# STM32F407VG.net
KiCad netlist of a schematic drawn in EasyEDA Pro
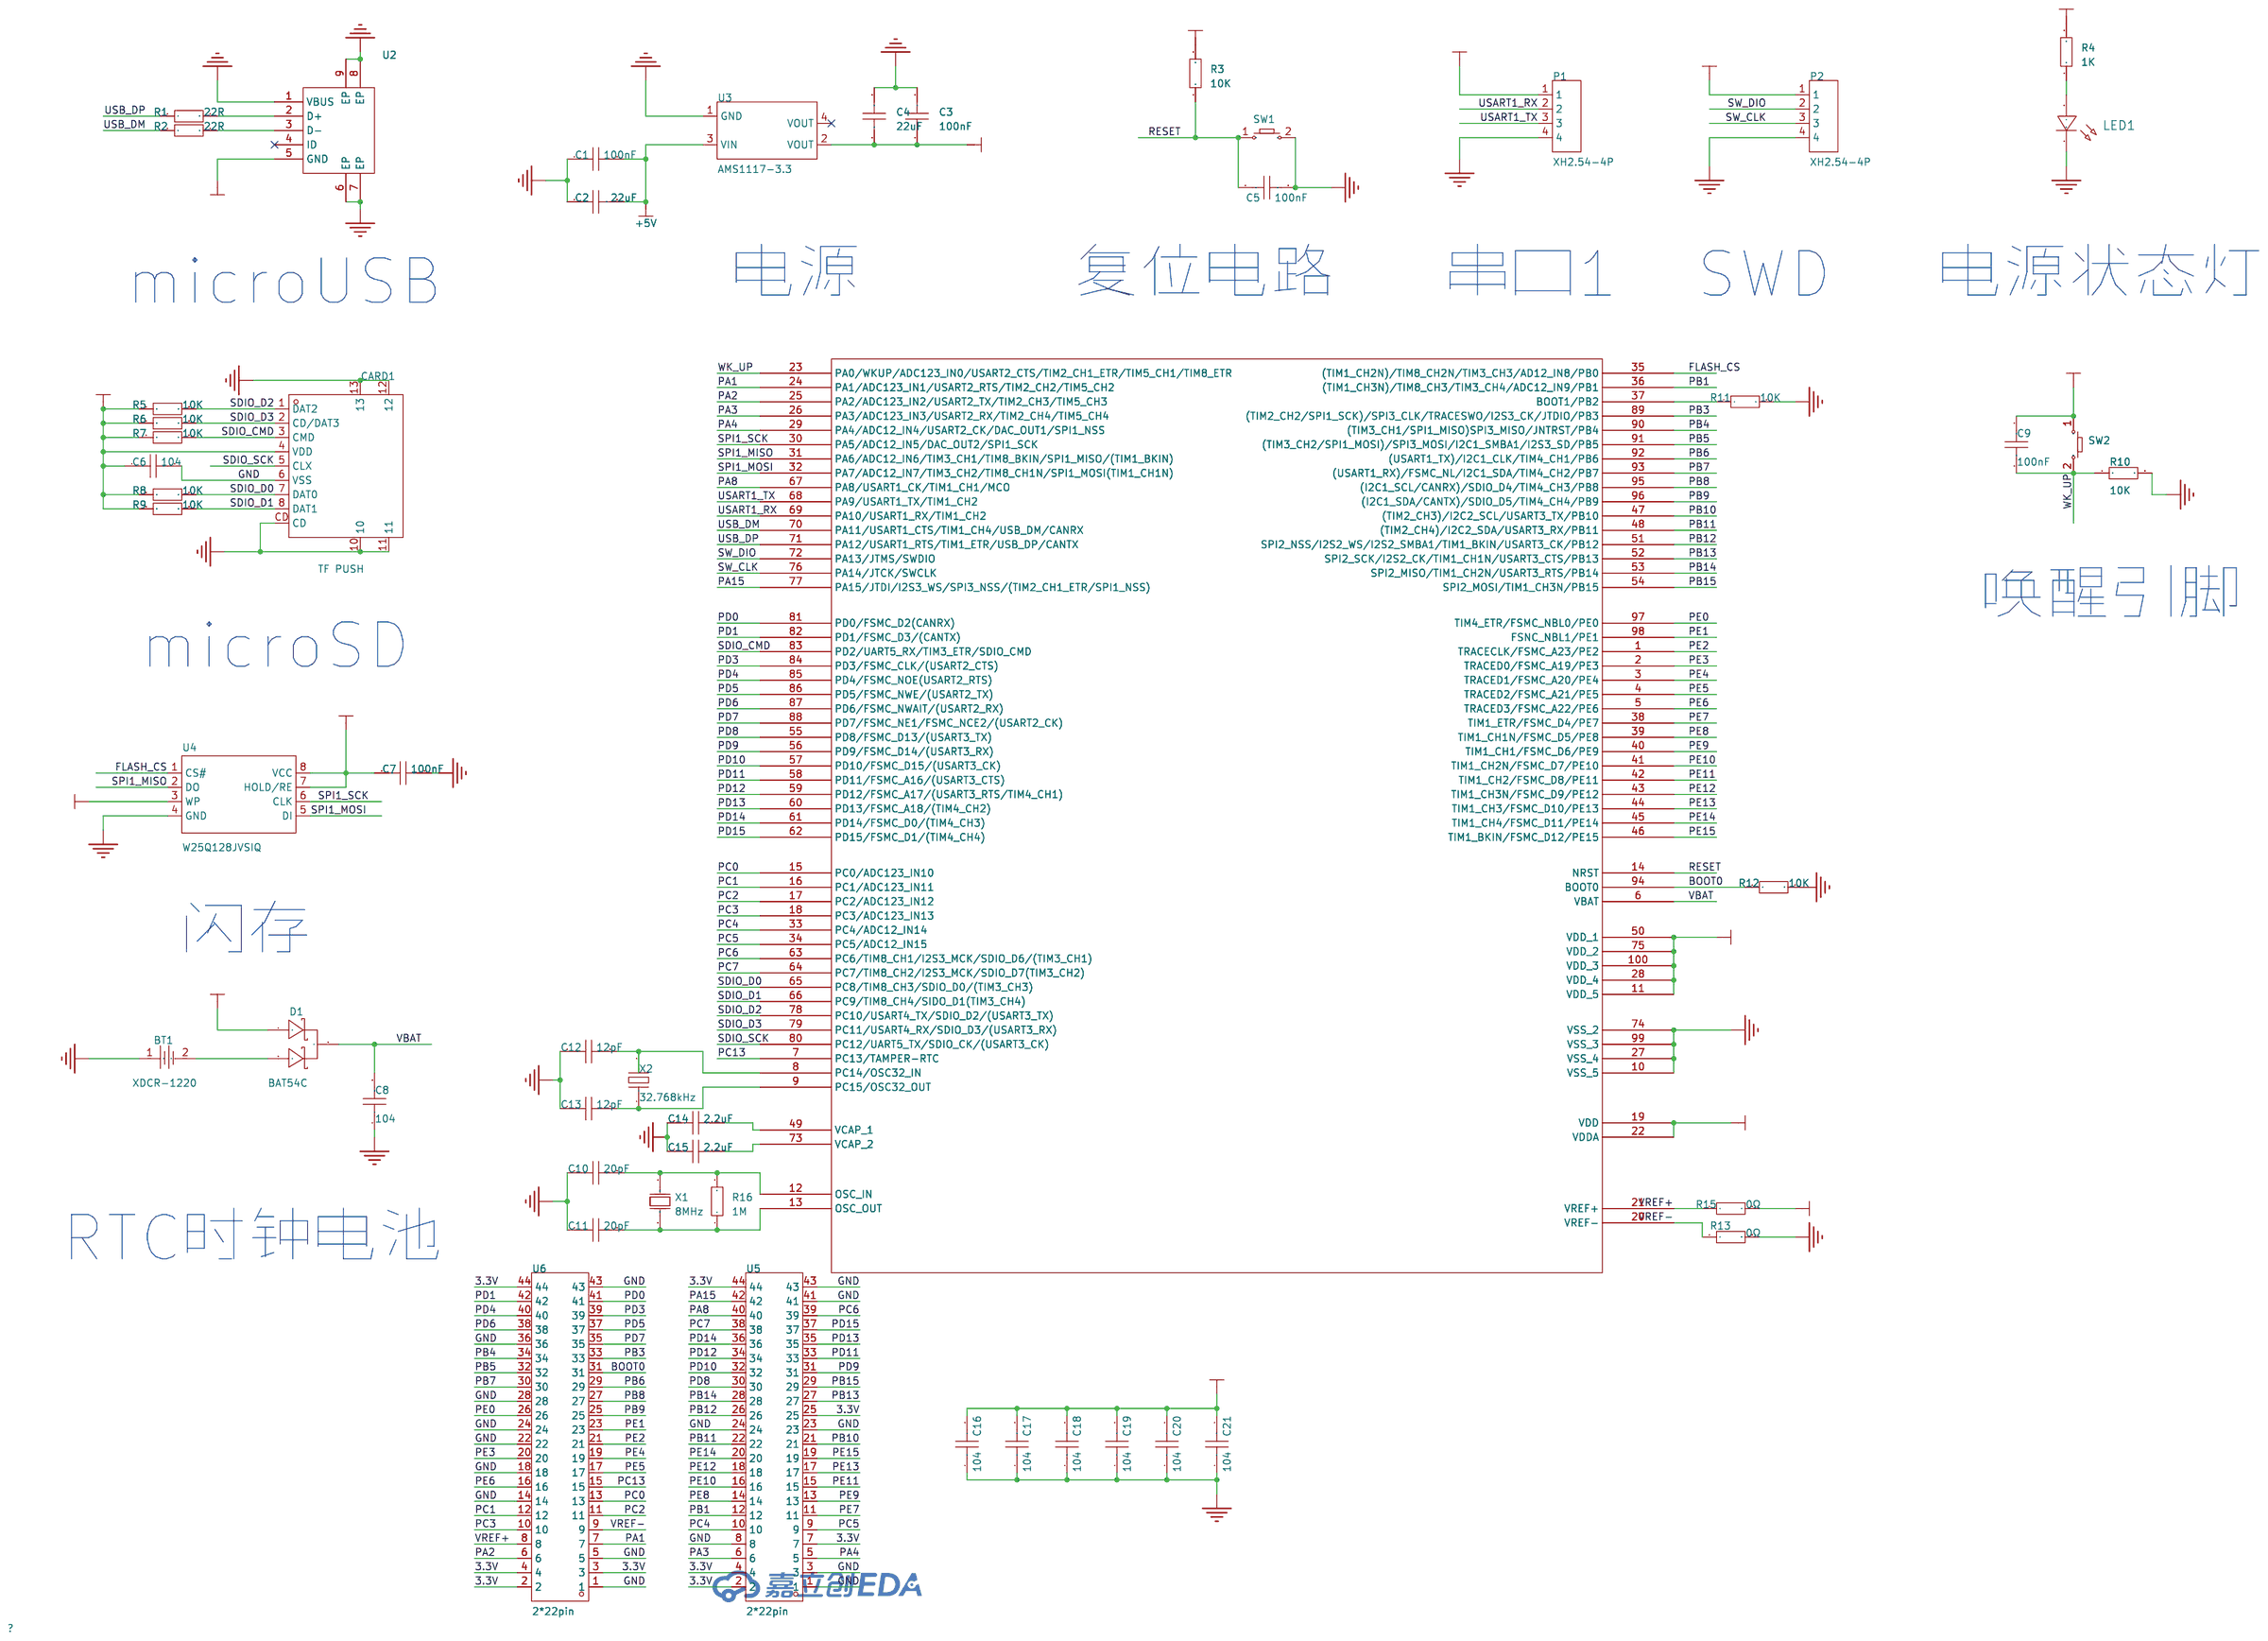
[diagram p0: schematic sheet]

(export (version "E")
  (design (tool "Eeschema 10.0.6"))
  (components
    (comp (ref "BT1")
      (value "XDCR-1220")
      (footprint "easyedapro:BAT-SMD_CR1220-2ZX")
      (description "连接器类型:电池底座;适用电池规格:CR1220;触头材质:-;触头镀层:金;工作温度:-40°C~+85°C;")
      (fields (field (name "Manufacturer") "LX(连欣科技)"))
      (libsource (lib "easyedapro") (part "XDCR-1220-006"))
    )
    (comp (ref "C1")
      (value "100nF")
      (footprint "easyedapro:C0603")
      (libsource (lib "easyedapro") (part "CapAcitance"))
    )
    (comp (ref "C2")
      (value "22uF")
      (footprint "easyedapro:C0603")
      (libsource (lib "easyedapro") (part "CapAcitance"))
    )
    (comp (ref "C3")
      (value "100nF")
      (footprint "easyedapro:C0603")
      (libsource (lib "easyedapro") (part "CapAcitance"))
    )
    (comp (ref "C4")
      (value "22uF")
      (footprint "easyedapro:C0603")
      (libsource (lib "easyedapro") (part "CapAcitance"))
    )
    (comp (ref "C5")
      (value "100nF")
      (footprint "easyedapro:C0603")
      (libsource (lib "easyedapro") (part "CapAcitance"))
    )
    (comp (ref "C6")
      (value "104")
      (footprint "easyedapro:C0603")
      (libsource (lib "easyedapro") (part "CapAcitance"))
    )
    (comp (ref "C7")
      (value "100nF")
      (footprint "easyedapro:C0603")
      (libsource (lib "easyedapro") (part "CapAcitance"))
    )
    (comp (ref "C8")
      (value "104")
      (footprint "easyedapro:C0603")
      (libsource (lib "easyedapro") (part "CapAcitance"))
    )
    (comp (ref "C9")
      (value "100nF")
      (footprint "easyedapro:C0603")
      (libsource (lib "easyedapro") (part "CapAcitance"))
    )
    (comp (ref "C10")
      (value "20pF")
      (footprint "easyedapro:C0603")
      (libsource (lib "easyedapro") (part "CapAcitance"))
    )
    (comp (ref "C11")
      (value "20pF")
      (footprint "easyedapro:C0603")
      (libsource (lib "easyedapro") (part "CapAcitance"))
    )
    (comp (ref "C12")
      (value "12pF")
      (footprint "easyedapro:C0603")
      (libsource (lib "easyedapro") (part "CapAcitance"))
    )
    (comp (ref "C13")
      (value "12pF")
      (footprint "easyedapro:C0603")
      (libsource (lib "easyedapro") (part "CapAcitance"))
    )
    (comp (ref "C14")
      (value "2.2uF")
      (footprint "easyedapro:C0603")
      (libsource (lib "easyedapro") (part "CapAcitance"))
    )
    (comp (ref "C15")
      (value "2.2uF")
      (footprint "easyedapro:C0603")
      (libsource (lib "easyedapro") (part "CapAcitance"))
    )
    (comp (ref "C16")
      (value "104")
      (footprint "easyedapro:C0603")
      (libsource (lib "easyedapro") (part "CapAcitance"))
    )
    (comp (ref "C17")
      (value "104")
      (footprint "easyedapro:C0603")
      (libsource (lib "easyedapro") (part "CapAcitance"))
    )
    (comp (ref "C18")
      (value "104")
      (footprint "easyedapro:C0603")
      (libsource (lib "easyedapro") (part "CapAcitance"))
    )
    (comp (ref "C19")
      (value "104")
      (footprint "easyedapro:C0603")
      (libsource (lib "easyedapro") (part "CapAcitance"))
    )
    (comp (ref "C20")
      (value "104")
      (footprint "easyedapro:C0603")
      (libsource (lib "easyedapro") (part "CapAcitance"))
    )
    (comp (ref "C21")
      (value "104")
      (footprint "easyedapro:C0603")
      (libsource (lib "easyedapro") (part "CapAcitance"))
    )
    (comp (ref "CARD1")
      (value "TF PUSH")
      (footprint "easyedapro:TF-SMD_TF-PUSH")
      (description "卡连接方式:自弹式;卡类型:MicroSD卡(TF卡);连接器类型:卡座;本体最大高度:2mm;工作温度:-25°C~+90°C;")
      (fields (field (name "Manufacturer") "SHOU HAN(首韩)"))
      (libsource (lib "easyedapro") (part "TF PUSH"))
    )
    (comp (ref "D1")
      (value "BAT54C")
      (footprint "easyedapro:SOT-23-3_L2.9-W1.6-P1.90-LS2.8-BR")
      (description "二极管配置:1对共阴极;正向压降(Vf):800mV@100mA;直流反向耐压(Vr):30V;整流电流:200mA;")
      (fields (field (name "Manufacturer") "Nexperia(安世)"))
      (libsource (lib "easyedapro") (part "BAT54C,215"))
    )
    (comp (ref "LED1")
      (value "~")
      (footprint "easyedapro:LED_0603")
      (libsource (lib "easyedapro") (part "LED_R"))
    )
    (comp (ref "P1")
      (value "XH2.54-4P")
      (footprint "easyedapro:CONN-TH_4P-P2.50-XH2.54-4P")
      (libsource (lib "easyedapro") (part "XH2.54-4P"))
    )
    (comp (ref "P2")
      (value "XH2.54-4P")
      (footprint "easyedapro:CONN-TH_4P-P2.50-XH2.54-4P")
      (libsource (lib "easyedapro") (part "XH2.54-4P"))
    )
    (comp (ref "R1")
      (value "22R")
      (footprint "easyedapro:Res_1/8W")
      (libsource (lib "easyedapro") (part "电阻"))
    )
    (comp (ref "R2")
      (value "22R")
      (footprint "easyedapro:Res_1/8W")
      (libsource (lib "easyedapro") (part "电阻"))
    )
    (comp (ref "R3")
      (value "10K")
      (footprint "easyedapro:Res_1/8W")
      (libsource (lib "easyedapro") (part "电阻"))
    )
    (comp (ref "R4")
      (value "1K")
      (footprint "easyedapro:Res_1/8W")
      (libsource (lib "easyedapro") (part "电阻"))
    )
    (comp (ref "R5")
      (value "10K")
      (footprint "easyedapro:Res_1/8W")
      (libsource (lib "easyedapro") (part "电阻"))
    )
    (comp (ref "R6")
      (value "10K")
      (footprint "easyedapro:Res_1/8W")
      (libsource (lib "easyedapro") (part "电阻"))
    )
    (comp (ref "R7")
      (value "10K")
      (footprint "easyedapro:Res_1/8W")
      (libsource (lib "easyedapro") (part "电阻"))
    )
    (comp (ref "R8")
      (value "10K")
      (footprint "easyedapro:Res_1/8W")
      (libsource (lib "easyedapro") (part "电阻"))
    )
    (comp (ref "R9")
      (value "10K")
      (footprint "easyedapro:Res_1/8W")
      (libsource (lib "easyedapro") (part "电阻"))
    )
    (comp (ref "R10")
      (value "10K")
      (footprint "easyedapro:Res_1/8W")
      (libsource (lib "easyedapro") (part "电阻"))
    )
    (comp (ref "R11")
      (value "10K")
      (footprint "easyedapro:Res_1/8W")
      (libsource (lib "easyedapro") (part "电阻"))
    )
    (comp (ref "R12")
      (value "10K")
      (footprint "easyedapro:Res_1/8W")
      (libsource (lib "easyedapro") (part "电阻"))
    )
    (comp (ref "R13")
      (value "0Ω")
      (footprint "easyedapro:Res_1/8W")
      (libsource (lib "easyedapro") (part "电阻"))
    )
    (comp (ref "R15")
      (value "0Ω")
      (footprint "easyedapro:Res_1/8W")
      (libsource (lib "easyedapro") (part "电阻"))
    )
    (comp (ref "R16")
      (value "1M")
      (footprint "easyedapro:Res_1/8W")
      (libsource (lib "easyedapro") (part "电阻"))
    )
    (comp (ref "SW1")
      (value "~")
      (footprint "easyedapro:Key_SMD_3x4x2")
      (libsource (lib "easyedapro") (part "轻触按键x2"))
    )
    (comp (ref "SW2")
      (value "~")
      (footprint "easyedapro:Key_SMD_3x4x2")
      (libsource (lib "easyedapro") (part "轻触按键x2"))
    )
    (comp (ref "U1")
      (value "STM32F407VGT6")
      (footprint "easyedapro:F407VG100P_TEST")
      (libsource (lib "easyedapro") (part "STM32F407VGT6"))
    )
    (comp (ref "U2")
      (value "USB-Micro-5P")
      (footprint "easyedapro:MICRO-USB-SMD_MICRO-USB-A9")
      (libsource (lib "easyedapro") (part "USB-MICRO-5P"))
    )
    (comp (ref "U3")
      (value "AMS1117-3.3")
      (footprint "easyedapro:SOT-223-3_L6.5-W3.4-P2.30-LS7.0-BR")
      (description "输出类型:固定;工作电压:16V;输出电压:3.3V;输出电流:1A;电源纹波抑制比(PSRR):72dB@(120Hz);输出极性:正极;")
      (fields (field (name "Manufacturer") "AMS"))
      (libsource (lib "easyedapro") (part "AMS1117-3.3"))
    )
    (comp (ref "U4")
      (value "W25Q128JVSIQ")
      (footprint "easyedapro:SOIC-8_L5.3-W5.3-P1.27-LS8.0-BL")
      (description "接口类型:SPI;存储容量:128Mbit;时钟频率(fc):133MHz;")
      (fields (field (name "Manufacturer") "Winbond(华邦)"))
      (libsource (lib "easyedapro") (part "W25Q128JVSIQTR"))
    )
    (comp (ref "U5")
      (value "2*22pin")
      (footprint "easyedapro:HDR-TH_44P-2.54-V-F-R2-C22-S2.54")
      (description "插孔结构:2x22P;间距:2.54mm;行距:2.54mm;安装方式:直插;排数:双排;总孔位数:44P;插孔方向:顶部;塑高:8.5mm;")
      (fields (field (name "Manufacturer") "CST(永丰盈)"))
      (libsource (lib "easyedapro") (part "CS-1166SDIG-2X22(H8.5)"))
    )
    (comp (ref "U6")
      (value "2*22pin")
      (footprint "easyedapro:HDR-TH_44P-2.54-V-F-R2-C22-S2.54")
      (description "插孔结构:2x22P;间距:2.54mm;行距:2.54mm;安装方式:直插;排数:双排;总孔位数:44P;插孔方向:顶部;塑高:8.5mm;")
      (fields (field (name "Manufacturer") "CST(永丰盈)"))
      (libsource (lib "easyedapro") (part "CS-1166SDIG-2X22(H8.5)"))
    )
    (comp (ref "X1")
      (value "8MHz")
      (footprint "easyedapro:OSC-TH_L10.0-W4.5-P5.00")
      (description "晶振类型:直插晶振;频率:8MHz;常温频差:±20ppm;负载电容:20pF;频率稳定度:±30ppm;")
      (fields (field (name "Manufacturer Part") "X49SD8MSD2SC") (field (name "Manufacturer") "YXC(扬兴晶振)"))
      (libsource (lib "easyedapro") (part "X49SD8MSD2SC"))
    )
    (comp (ref "X2")
      (value "32.768kHz")
      (footprint "easyedapro:OSC-SMD_L3.2-W1.5")
      (description "晶振类型:贴片晶振;频率:32.768kHz;常温频差:±20ppm;负载电容:12.5pF;频率稳定度:±30ppm;")
      (fields (field (name "Manufacturer Part") "X321532768KGD2SI") (field (name "Manufacturer") "YXC(扬兴晶振)"))
      (libsource (lib "easyedapro") (part "X321532768KGD2SI"))
    )
  )
  (nets
    (net (code "1") (name "+5V") (class "Default")
      (node (ref "C1") (pin "2") (pinfunction "2_2") (pintype "input"))
      (node (ref "C2") (pin "2") (pinfunction "2_2") (pintype "input"))
      (node (ref "U2") (pin "5") (pinfunction "GND_5") (pintype "unspecified"))
      (node (ref "U3") (pin "3") (pinfunction "VIN_3") (pintype "unspecified"))
    )
    (net (code "2") (name "/BOOT0") (class "Default")
      (node (ref "R12") (pin "1") (pinfunction "1_1") (pintype "input"))
      (node (ref "U1") (pin "94") (pinfunction "BOOT0_94") (pintype "input"))
      (node (ref "U6") (pin "31") (pinfunction "31_31") (pintype "unspecified"))
    )
    (net (code "3") (name "/FLASH_CS") (class "Default")
      (node (ref "U1") (pin "35") (pinfunction "(TIM1_CH2N)/TIM8_CH2N/TIM3_CH3/AD12_IN8/PB0_35") (pintype "input"))
      (node (ref "U4") (pin "1") (pinfunction "CS#_1") (pintype "unspecified"))
    )
    (net (code "4") (name "/PA1") (class "Default")
      (node (ref "U1") (pin "24") (pinfunction "PA1/ADC123_IN1/USART2_RTS/TIM2_CH2/TIM5_CH2_24") (pintype "input"))
      (node (ref "U6") (pin "7") (pinfunction "7_7") (pintype "unspecified"))
    )
    (net (code "5") (name "/PA2") (class "Default")
      (node (ref "U1") (pin "25") (pinfunction "PA2/ADC123_IN2/USART2_TX/TIM2_CH3/TIM5_CH3_25") (pintype "input"))
      (node (ref "U6") (pin "6") (pinfunction "6_6") (pintype "unspecified"))
    )
    (net (code "6") (name "/PA3") (class "Default")
      (node (ref "U1") (pin "26") (pinfunction "PA3/ADC123_IN3/USART2_RX/TIM2_CH4/TIM5_CH4_26") (pintype "input"))
      (node (ref "U5") (pin "6") (pinfunction "6_6") (pintype "unspecified"))
    )
    (net (code "7") (name "/PA4") (class "Default")
      (node (ref "U1") (pin "29") (pinfunction "PA4/ADC12_IN4/USART2_CK/DAC_OUT1/SPI1_NSS_29") (pintype "input"))
      (node (ref "U5") (pin "5") (pinfunction "5_5") (pintype "unspecified"))
    )
    (net (code "8") (name "/PA8") (class "Default")
      (node (ref "U1") (pin "67") (pinfunction "PA8/USART1_CK/TIM1_CH1/MCO_67") (pintype "input"))
      (node (ref "U5") (pin "40") (pinfunction "40_40") (pintype "unspecified"))
    )
    (net (code "9") (name "/PA15") (class "Default")
      (node (ref "U1") (pin "77") (pinfunction "PA15/JTDI/I2S3_WS/SPI3_NSS/(TIM2_CH1_ETR/SPI1_NSS)_77") (pintype "input"))
      (node (ref "U5") (pin "42") (pinfunction "42_42") (pintype "unspecified"))
    )
    (net (code "10") (name "/PB1") (class "Default")
      (node (ref "U1") (pin "36") (pinfunction "(TIM1_CH3N)/TIM8_CH3/TIM3_CH4/ADC12_IN9/PB1_36") (pintype "input"))
      (node (ref "U5") (pin "12") (pinfunction "12_12") (pintype "unspecified"))
    )
    (net (code "11") (name "/PB3") (class "Default")
      (node (ref "U1") (pin "89") (pinfunction "(TIM2_CH2/SPI1_SCK)/SPI3_CLK/TRACESWO/I2S3_CK/JTDIO/PB3_89") (pintype "input"))
      (node (ref "U6") (pin "33") (pinfunction "33_33") (pintype "unspecified"))
    )
    (net (code "12") (name "/PB4") (class "Default")
      (node (ref "U1") (pin "90") (pinfunction "(TIM3_CH1/SPI1_MISO)SPI3_MISO/JNTRST/PB4_90") (pintype "input"))
      (node (ref "U6") (pin "34") (pinfunction "34_34") (pintype "unspecified"))
    )
    (net (code "13") (name "/PB5") (class "Default")
      (node (ref "U1") (pin "91") (pinfunction "(TIM3_CH2/SPI1_MOSI)/SPI3_MOSI/I2C1_SMBA1/I2S3_SD/PB5_91") (pintype "input"))
      (node (ref "U6") (pin "32") (pinfunction "32_32") (pintype "unspecified"))
    )
    (net (code "14") (name "/PB6") (class "Default")
      (node (ref "U1") (pin "92") (pinfunction "(USART1_TX)/I2C1_CLK/TIM4_CH1/PB6_92") (pintype "input"))
      (node (ref "U6") (pin "29") (pinfunction "29_29") (pintype "unspecified"))
    )
    (net (code "15") (name "/PB7") (class "Default")
      (node (ref "U1") (pin "93") (pinfunction "(USART1_RX)/FSMC_NL/I2C1_SDA/TIM4_CH2/PB7_93") (pintype "input"))
      (node (ref "U6") (pin "30") (pinfunction "30_30") (pintype "unspecified"))
    )
    (net (code "16") (name "/PB8") (class "Default")
      (node (ref "U1") (pin "95") (pinfunction "(I2C1_SCL/CANRX)/SDIO_D4/TIM4_CH3/PB8_95") (pintype "input"))
      (node (ref "U6") (pin "27") (pinfunction "27_27") (pintype "unspecified"))
    )
    (net (code "17") (name "/PB9") (class "Default")
      (node (ref "U1") (pin "96") (pinfunction "(I2C1_SDA/CANTX)/SDIO_D5/TIM4_CH4/PB9_96") (pintype "input"))
      (node (ref "U6") (pin "25") (pinfunction "25_25") (pintype "unspecified"))
    )
    (net (code "18") (name "/PB10") (class "Default")
      (node (ref "U1") (pin "47") (pinfunction "(TIM2_CH3)/I2C2_SCL/USART3_TX/PB10_47") (pintype "input"))
      (node (ref "U5") (pin "21") (pinfunction "21_21") (pintype "unspecified"))
    )
    (net (code "19") (name "/PB11") (class "Default")
      (node (ref "U1") (pin "48") (pinfunction "(TIM2_CH4)/I2C2_SDA/USART3_RX/PB11_48") (pintype "input"))
      (node (ref "U5") (pin "22") (pinfunction "22_22") (pintype "unspecified"))
    )
    (net (code "20") (name "/PB12") (class "Default")
      (node (ref "U1") (pin "51") (pinfunction "SPI2_NSS/I2S2_WS/I2S2_SMBA1/TIM1_BKIN/USART3_CK/PB12_51") (pintype "input"))
      (node (ref "U5") (pin "26") (pinfunction "26_26") (pintype "unspecified"))
    )
    (net (code "21") (name "/PB13") (class "Default")
      (node (ref "U1") (pin "52") (pinfunction "SPI2_SCK/I2S2_CK/TIM1_CH1N/USART3_CTS/PB13_52") (pintype "input"))
      (node (ref "U5") (pin "27") (pinfunction "27_27") (pintype "unspecified"))
    )
    (net (code "22") (name "/PB14") (class "Default")
      (node (ref "U1") (pin "53") (pinfunction "SPI2_MISO/TIM1_CH2N/USART3_RTS/PB14_53") (pintype "input"))
      (node (ref "U5") (pin "28") (pinfunction "28_28") (pintype "unspecified"))
    )
    (net (code "23") (name "/PB15") (class "Default")
      (node (ref "U1") (pin "54") (pinfunction "SPI2_MOSI/TIM1_CH3N/PB15_54") (pintype "input"))
      (node (ref "U5") (pin "29") (pinfunction "29_29") (pintype "unspecified"))
    )
    (net (code "24") (name "/PC0") (class "Default")
      (node (ref "U1") (pin "15") (pinfunction "PC0/ADC123_IN10_15") (pintype "input"))
      (node (ref "U6") (pin "13") (pinfunction "13_13") (pintype "unspecified"))
    )
    (net (code "25") (name "/PC1") (class "Default")
      (node (ref "U1") (pin "16") (pinfunction "PC1/ADC123_IN11_16") (pintype "input"))
      (node (ref "U6") (pin "12") (pinfunction "12_12") (pintype "unspecified"))
    )
    (net (code "26") (name "/PC2") (class "Default")
      (node (ref "U1") (pin "17") (pinfunction "PC2/ADC123_IN12_17") (pintype "input"))
      (node (ref "U6") (pin "11") (pinfunction "11_11") (pintype "unspecified"))
    )
    (net (code "27") (name "/PC3") (class "Default")
      (node (ref "U1") (pin "18") (pinfunction "PC3/ADC123_IN13_18") (pintype "input"))
      (node (ref "U6") (pin "10") (pinfunction "10_10") (pintype "unspecified"))
    )
    (net (code "28") (name "/PC4") (class "Default")
      (node (ref "U1") (pin "33") (pinfunction "PC4/ADC12_IN14_33") (pintype "input"))
      (node (ref "U5") (pin "10") (pinfunction "10_10") (pintype "unspecified"))
    )
    (net (code "29") (name "/PC5") (class "Default")
      (node (ref "U1") (pin "34") (pinfunction "PC5/ADC12_IN15_34") (pintype "input"))
      (node (ref "U5") (pin "9") (pinfunction "9_9") (pintype "unspecified"))
    )
    (net (code "30") (name "/PC6") (class "Default")
      (node (ref "U1") (pin "63") (pinfunction "PC6/TIM8_CH1/I2S3_MCK/SDIO_D6/(TIM3_CH1)_63") (pintype "input"))
      (node (ref "U5") (pin "39") (pinfunction "39_39") (pintype "unspecified"))
    )
    (net (code "31") (name "/PC7") (class "Default")
      (node (ref "U1") (pin "64") (pinfunction "PC7/TIM8_CH2/I2S3_MCK/SDIO_D7(TIM3_CH2)_64") (pintype "input"))
      (node (ref "U5") (pin "38") (pinfunction "38_38") (pintype "unspecified"))
    )
    (net (code "32") (name "/PC13") (class "Default")
      (node (ref "U1") (pin "7") (pinfunction "PC13/TAMPER-RTC_7") (pintype "input"))
      (node (ref "U6") (pin "15") (pinfunction "15_15") (pintype "unspecified"))
    )
    (net (code "33") (name "/PD0") (class "Default")
      (node (ref "U1") (pin "81") (pinfunction "PD0/FSMC_D2(CANRX)_81") (pintype "input"))
      (node (ref "U6") (pin "41") (pinfunction "41_41") (pintype "unspecified"))
    )
    (net (code "34") (name "/PD1") (class "Default")
      (node (ref "U1") (pin "82") (pinfunction "PD1/FSMC_D3/(CANTX)_82") (pintype "input"))
      (node (ref "U6") (pin "42") (pinfunction "42_42") (pintype "unspecified"))
    )
    (net (code "35") (name "/PD3") (class "Default")
      (node (ref "U1") (pin "84") (pinfunction "PD3/FSMC_CLK/(USART2_CTS)_84") (pintype "input"))
      (node (ref "U6") (pin "39") (pinfunction "39_39") (pintype "unspecified"))
    )
    (net (code "36") (name "/PD4") (class "Default")
      (node (ref "U1") (pin "85") (pinfunction "PD4/FSMC_NOE(USART2_RTS)_85") (pintype "input"))
      (node (ref "U6") (pin "40") (pinfunction "40_40") (pintype "unspecified"))
    )
    (net (code "37") (name "/PD5") (class "Default")
      (node (ref "U1") (pin "86") (pinfunction "PD5/FSMC_NWE/(USART2_TX)_86") (pintype "input"))
      (node (ref "U6") (pin "37") (pinfunction "37_37") (pintype "unspecified"))
    )
    (net (code "38") (name "/PD6") (class "Default")
      (node (ref "U1") (pin "87") (pinfunction "PD6/FSMC_NWAIT/(USART2_RX)_87") (pintype "input"))
      (node (ref "U6") (pin "38") (pinfunction "38_38") (pintype "unspecified"))
    )
    (net (code "39") (name "/PD7") (class "Default")
      (node (ref "U1") (pin "88") (pinfunction "PD7/FSMC_NE1/FSMC_NCE2/(USART2_CK)_88") (pintype "input"))
      (node (ref "U6") (pin "35") (pinfunction "35_35") (pintype "unspecified"))
    )
    (net (code "40") (name "/PD8") (class "Default")
      (node (ref "U1") (pin "55") (pinfunction "PD8/FSMC_D13/(USART3_TX)_55") (pintype "input"))
      (node (ref "U5") (pin "30") (pinfunction "30_30") (pintype "unspecified"))
    )
    (net (code "41") (name "/PD9") (class "Default")
      (node (ref "U1") (pin "56") (pinfunction "PD9/FSMC_D14/(USART3_RX)_56") (pintype "input"))
      (node (ref "U5") (pin "31") (pinfunction "31_31") (pintype "unspecified"))
    )
    (net (code "42") (name "/PD10") (class "Default")
      (node (ref "U1") (pin "57") (pinfunction "PD10/FSMC_D15/(USART3_CK)_57") (pintype "input"))
      (node (ref "U5") (pin "32") (pinfunction "32_32") (pintype "unspecified"))
    )
    (net (code "43") (name "/PD11") (class "Default")
      (node (ref "U1") (pin "58") (pinfunction "PD11/FSMC_A16/(USART3_CTS)_58") (pintype "input"))
      (node (ref "U5") (pin "33") (pinfunction "33_33") (pintype "unspecified"))
    )
    (net (code "44") (name "/PD12") (class "Default")
      (node (ref "U1") (pin "59") (pinfunction "PD12/FSMC_A17/(USART3_RTS/TIM4_CH1)_59") (pintype "input"))
      (node (ref "U5") (pin "34") (pinfunction "34_34") (pintype "unspecified"))
    )
    (net (code "45") (name "/PD13") (class "Default")
      (node (ref "U1") (pin "60") (pinfunction "PD13/FSMC_A18/(TIM4_CH2)_60") (pintype "input"))
      (node (ref "U5") (pin "35") (pinfunction "35_35") (pintype "unspecified"))
    )
    (net (code "46") (name "/PD14") (class "Default")
      (node (ref "U1") (pin "61") (pinfunction "PD14/FSMC_D0/(TIM4_CH3)_61") (pintype "input"))
      (node (ref "U5") (pin "36") (pinfunction "36_36") (pintype "unspecified"))
    )
    (net (code "47") (name "/PD15") (class "Default")
      (node (ref "U1") (pin "62") (pinfunction "PD15/FSMC_D1/(TIM4_CH4)_62") (pintype "input"))
      (node (ref "U5") (pin "37") (pinfunction "37_37") (pintype "unspecified"))
    )
    (net (code "48") (name "/PE0") (class "Default")
      (node (ref "U1") (pin "97") (pinfunction "TIM4_ETR/FSMC_NBL0/PE0_97") (pintype "input"))
      (node (ref "U6") (pin "26") (pinfunction "26_26") (pintype "unspecified"))
    )
    (net (code "49") (name "/PE1") (class "Default")
      (node (ref "U1") (pin "98") (pinfunction "FSNC_NBL1/PE1_98") (pintype "input"))
      (node (ref "U6") (pin "23") (pinfunction "23_23") (pintype "unspecified"))
    )
    (net (code "50") (name "/PE2") (class "Default")
      (node (ref "U1") (pin "1") (pinfunction "TRACECLK/FSMC_A23/PE2_1") (pintype "input"))
      (node (ref "U6") (pin "21") (pinfunction "21_21") (pintype "unspecified"))
    )
    (net (code "51") (name "/PE3") (class "Default")
      (node (ref "U1") (pin "2") (pinfunction "TRACED0/FSMC_A19/PE3_2") (pintype "input"))
      (node (ref "U6") (pin "20") (pinfunction "20_20") (pintype "unspecified"))
    )
    (net (code "52") (name "/PE4") (class "Default")
      (node (ref "U1") (pin "3") (pinfunction "TRACED1/FSMC_A20/PE4_3") (pintype "input"))
      (node (ref "U6") (pin "19") (pinfunction "19_19") (pintype "unspecified"))
    )
    (net (code "53") (name "/PE5") (class "Default")
      (node (ref "U1") (pin "4") (pinfunction "TRACED2/FSMC_A21/PE5_4") (pintype "input"))
      (node (ref "U6") (pin "17") (pinfunction "17_17") (pintype "unspecified"))
    )
    (net (code "54") (name "/PE6") (class "Default")
      (node (ref "U1") (pin "5") (pinfunction "TRACED3/FSMC_A22/PE6_5") (pintype "input"))
      (node (ref "U6") (pin "16") (pinfunction "16_16") (pintype "unspecified"))
    )
    (net (code "55") (name "/PE7") (class "Default")
      (node (ref "U1") (pin "38") (pinfunction "TIM1_ETR/FSMC_D4/PE7_38") (pintype "input"))
      (node (ref "U5") (pin "11") (pinfunction "11_11") (pintype "unspecified"))
    )
    (net (code "56") (name "/PE8") (class "Default")
      (node (ref "U1") (pin "39") (pinfunction "TIM1_CH1N/FSMC_D5/PE8_39") (pintype "input"))
      (node (ref "U5") (pin "14") (pinfunction "14_14") (pintype "unspecified"))
    )
    (net (code "57") (name "/PE9") (class "Default")
      (node (ref "U1") (pin "40") (pinfunction "TIM1_CH1/FSMC_D6/PE9_40") (pintype "input"))
      (node (ref "U5") (pin "13") (pinfunction "13_13") (pintype "unspecified"))
    )
    (net (code "58") (name "/PE10") (class "Default")
      (node (ref "U1") (pin "41") (pinfunction "TIM1_CH2N/FSMC_D7/PE10_41") (pintype "input"))
      (node (ref "U5") (pin "16") (pinfunction "16_16") (pintype "unspecified"))
    )
    (net (code "59") (name "/PE11") (class "Default")
      (node (ref "U1") (pin "42") (pinfunction "TIM1_CH2/FSMC_D8/PE11_42") (pintype "input"))
      (node (ref "U5") (pin "15") (pinfunction "15_15") (pintype "unspecified"))
    )
    (net (code "60") (name "/PE12") (class "Default")
      (node (ref "U1") (pin "43") (pinfunction "TIM1_CH3N/FSMC_D9/PE12_43") (pintype "input"))
      (node (ref "U5") (pin "18") (pinfunction "18_18") (pintype "unspecified"))
    )
    (net (code "61") (name "/PE13") (class "Default")
      (node (ref "U1") (pin "44") (pinfunction "TIM1_CH3/FSMC_D10/PE13_44") (pintype "input"))
      (node (ref "U5") (pin "17") (pinfunction "17_17") (pintype "unspecified"))
    )
    (net (code "62") (name "/PE14") (class "Default")
      (node (ref "U1") (pin "45") (pinfunction "TIM1_CH4/FSMC_D11/PE14_45") (pintype "input"))
      (node (ref "U5") (pin "20") (pinfunction "20_20") (pintype "unspecified"))
    )
    (net (code "63") (name "/PE15") (class "Default")
      (node (ref "U1") (pin "46") (pinfunction "TIM1_BKIN/FSMC_D12/PE15_46") (pintype "input"))
      (node (ref "U5") (pin "19") (pinfunction "19_19") (pintype "unspecified"))
    )
    (net (code "64") (name "/RESET") (class "Default")
      (node (ref "C5") (pin "1") (pinfunction "1_1") (pintype "input"))
      (node (ref "R3") (pin "2") (pinfunction "2_2") (pintype "input"))
      (node (ref "SW1") (pin "1") (pinfunction "1_1") (pintype "input"))
      (node (ref "U1") (pin "14") (pinfunction "NRST_14") (pintype "input"))
    )
    (net (code "65") (name "/SDIO_CMD") (class "Default")
      (node (ref "CARD1") (pin "3") (pinfunction "CMD_3") (pintype "unspecified"))
      (node (ref "R7") (pin "2") (pinfunction "2_2") (pintype "input"))
      (node (ref "U1") (pin "83") (pinfunction "PD2/UART5_RX/TIM3_ETR/SDIO_CMD_83") (pintype "input"))
    )
    (net (code "66") (name "/SDIO_D0") (class "Default")
      (node (ref "CARD1") (pin "7") (pinfunction "DAT0_7") (pintype "unspecified"))
      (node (ref "R8") (pin "2") (pinfunction "2_2") (pintype "input"))
      (node (ref "U1") (pin "65") (pinfunction "PC8/TIM8_CH3/SDIO_D0/(TIM3_CH3)_65") (pintype "input"))
    )
    (net (code "67") (name "/SDIO_D1") (class "Default")
      (node (ref "CARD1") (pin "8") (pinfunction "DAT1_8") (pintype "unspecified"))
      (node (ref "R9") (pin "2") (pinfunction "2_2") (pintype "input"))
      (node (ref "U1") (pin "66") (pinfunction "PC9/TIM8_CH4/SIDO_D1(TIM3_CH4)_66") (pintype "input"))
    )
    (net (code "68") (name "/SDIO_D2") (class "Default")
      (node (ref "CARD1") (pin "1") (pinfunction "DAT2_1") (pintype "unspecified"))
      (node (ref "R5") (pin "2") (pinfunction "2_2") (pintype "input"))
      (node (ref "U1") (pin "78") (pinfunction "PC10/USART4_TX/SDIO_D2/(USART3_TX)_78") (pintype "input"))
    )
    (net (code "69") (name "/SDIO_D3") (class "Default")
      (node (ref "CARD1") (pin "2") (pinfunction "CD/DAT3_2") (pintype "unspecified"))
      (node (ref "R6") (pin "2") (pinfunction "2_2") (pintype "input"))
      (node (ref "U1") (pin "79") (pinfunction "PC11/USART4_RX/SDIO_D3/(USART3_RX)_79") (pintype "input"))
    )
    (net (code "70") (name "/SDIO_SCK") (class "Default")
      (node (ref "CARD1") (pin "5") (pinfunction "CLX_5") (pintype "unspecified"))
      (node (ref "U1") (pin "80") (pinfunction "PC12/UART5_TX/SDIO_CK/(USART3_CK)_80") (pintype "input"))
    )
    (net (code "71") (name "/SPI1_MISO") (class "Default")
      (node (ref "U1") (pin "31") (pinfunction "PA6/ADC12_IN6/TIM3_CH1/TIM8_BKIN/SPI1_MISO/(TIM1_BKIN)_31") (pintype "input"))
      (node (ref "U4") (pin "2") (pinfunction "DO_2") (pintype "unspecified"))
    )
    (net (code "72") (name "/SPI1_MOSI") (class "Default")
      (node (ref "U1") (pin "32") (pinfunction "PA7/ADC12_IN7/TIM3_CH2/TIM8_CH1N/SPI1_MOSI(TIM1_CH1N)_32") (pintype "input"))
      (node (ref "U4") (pin "5") (pinfunction "DI_5") (pintype "unspecified"))
    )
    (net (code "73") (name "/SPI1_SCK") (class "Default")
      (node (ref "U1") (pin "30") (pinfunction "PA5/ADC12_IN5/DAC_OUT2/SPI1_SCK_30") (pintype "input"))
      (node (ref "U4") (pin "6") (pinfunction "CLK_6") (pintype "unspecified"))
    )
    (net (code "74") (name "/SW_CLK") (class "Default")
      (node (ref "P2") (pin "3") (pinfunction "3_3") (pintype "unspecified"))
      (node (ref "U1") (pin "76") (pinfunction "PA14/JTCK/SWCLK_76") (pintype "input"))
    )
    (net (code "75") (name "/SW_DIO") (class "Default")
      (node (ref "P2") (pin "2") (pinfunction "2_2") (pintype "unspecified"))
      (node (ref "U1") (pin "72") (pinfunction "PA13/JTMS/SWDIO_72") (pintype "input"))
    )
    (net (code "76") (name "/USART1_RX") (class "Default")
      (node (ref "P1") (pin "2") (pinfunction "2_2") (pintype "unspecified"))
      (node (ref "U1") (pin "69") (pinfunction "PA10/USART1_RX/TIM1_CH2_69") (pintype "input"))
    )
    (net (code "77") (name "/USART1_TX") (class "Default")
      (node (ref "P1") (pin "3") (pinfunction "3_3") (pintype "unspecified"))
      (node (ref "U1") (pin "68") (pinfunction "PA9/USART1_TX/TIM1_CH2_68") (pintype "input"))
    )
    (net (code "78") (name "/USB_DM") (class "Default")
      (node (ref "R2") (pin "1") (pinfunction "1_1") (pintype "input"))
      (node (ref "U1") (pin "70") (pinfunction "PA11/USART1_CTS/TIM1_CH4/USB_DM/CANRX_70") (pintype "input"))
    )
    (net (code "79") (name "/USB_DP") (class "Default")
      (node (ref "R1") (pin "1") (pinfunction "1_1") (pintype "input"))
      (node (ref "U1") (pin "71") (pinfunction "PA12/USART1_RTS/TIM1_ETR/USB_DP/CANTX_71") (pintype "input"))
    )
    (net (code "80") (name "/VBAT") (class "Default")
      (node (ref "C8") (pin "2") (pinfunction "2_2") (pintype "input"))
      (node (ref "D1") (pin "3") (pinfunction "K_3") (pintype "unspecified"))
      (node (ref "U1") (pin "6") (pinfunction "VBAT_6") (pintype "input"))
    )
    (net (code "81") (name "/VREF+") (class "Default")
      (node (ref "R15") (pin "1") (pinfunction "1_1") (pintype "input"))
      (node (ref "U1") (pin "21") (pinfunction "VREF+_21") (pintype "input"))
      (node (ref "U6") (pin "8") (pinfunction "8_8") (pintype "unspecified"))
    )
    (net (code "82") (name "/VREF-") (class "Default")
      (node (ref "R13") (pin "1") (pinfunction "1_1") (pintype "input"))
      (node (ref "U1") (pin "20") (pinfunction "VREF-_20") (pintype "input"))
      (node (ref "U6") (pin "9") (pinfunction "9_9") (pintype "unspecified"))
    )
    (net (code "83") (name "/WK_UP") (class "Default")
      (node (ref "C9") (pin "1") (pinfunction "1_1") (pintype "input"))
      (node (ref "R10") (pin "1") (pinfunction "1_1") (pintype "input"))
      (node (ref "SW2") (pin "2") (pinfunction "2_2") (pintype "input"))
      (node (ref "U1") (pin "23") (pinfunction "PA0/WKUP/ADC123_IN0/USART2_CTS/TIM2_CH1_ETR/TIM5_CH1/TIM8_ETR_23") (pintype "input"))
    )
    (net (code "84") (name "3.3V") (class "Default")
      (node (ref "C16") (pin "2") (pinfunction "2_2") (pintype "input"))
      (node (ref "C17") (pin "2") (pinfunction "2_2") (pintype "input"))
      (node (ref "C18") (pin "2") (pinfunction "2_2") (pintype "input"))
      (node (ref "C19") (pin "2") (pinfunction "2_2") (pintype "input"))
      (node (ref "C20") (pin "2") (pinfunction "2_2") (pintype "input"))
      (node (ref "C21") (pin "2") (pinfunction "2_2") (pintype "input"))
      (node (ref "C3") (pin "2") (pinfunction "2_2") (pintype "input"))
      (node (ref "C4") (pin "2") (pinfunction "2_2") (pintype "input"))
      (node (ref "C6") (pin "1") (pinfunction "1_1") (pintype "input"))
      (node (ref "C7") (pin "1") (pinfunction "1_1") (pintype "input"))
      (node (ref "C9") (pin "2") (pinfunction "2_2") (pintype "input"))
      (node (ref "CARD1") (pin "4") (pinfunction "VDD_4") (pintype "unspecified"))
      (node (ref "D1") (pin "1") (pinfunction "A_1") (pintype "unspecified"))
      (node (ref "P1") (pin "1") (pinfunction "1_1") (pintype "unspecified"))
      (node (ref "P2") (pin "1") (pinfunction "1_1") (pintype "unspecified"))
      (node (ref "R15") (pin "2") (pinfunction "2_2") (pintype "input"))
      (node (ref "R3") (pin "1") (pinfunction "1_1") (pintype "input"))
      (node (ref "R4") (pin "2") (pinfunction "2_2") (pintype "input"))
      (node (ref "R5") (pin "1") (pinfunction "1_1") (pintype "input"))
      (node (ref "R6") (pin "1") (pinfunction "1_1") (pintype "input"))
      (node (ref "R7") (pin "1") (pinfunction "1_1") (pintype "input"))
      (node (ref "R8") (pin "1") (pinfunction "1_1") (pintype "input"))
      (node (ref "R9") (pin "1") (pinfunction "1_1") (pintype "input"))
      (node (ref "SW2") (pin "1") (pinfunction "1_1") (pintype "input"))
      (node (ref "U1") (pin "100") (pinfunction "VDD_3_100") (pintype "input"))
      (node (ref "U1") (pin "11") (pinfunction "VDD_5_11") (pintype "input"))
      (node (ref "U1") (pin "19") (pinfunction "VDD_19") (pintype "input"))
      (node (ref "U1") (pin "22") (pinfunction "VDDA_22") (pintype "input"))
      (node (ref "U1") (pin "28") (pinfunction "VDD_4_28") (pintype "input"))
      (node (ref "U1") (pin "50") (pinfunction "VDD_1_50") (pintype "input"))
      (node (ref "U1") (pin "75") (pinfunction "VDD_2_75") (pintype "input"))
      (node (ref "U3") (pin "2") (pinfunction "VOUT_2") (pintype "unspecified"))
      (node (ref "U4") (pin "3") (pinfunction "WP_3") (pintype "unspecified"))
      (node (ref "U4") (pin "7") (pinfunction "HOLD/RE_7") (pintype "unspecified"))
      (node (ref "U4") (pin "8") (pinfunction "VCC_8") (pintype "unspecified"))
      (node (ref "U5") (pin "2") (pinfunction "2_2") (pintype "unspecified"))
      (node (ref "U5") (pin "25") (pinfunction "25_25") (pintype "unspecified"))
      (node (ref "U5") (pin "4") (pinfunction "4_4") (pintype "unspecified"))
      (node (ref "U5") (pin "44") (pinfunction "44_44") (pintype "unspecified"))
      (node (ref "U5") (pin "7") (pinfunction "7_7") (pintype "unspecified"))
      (node (ref "U6") (pin "2") (pinfunction "2_2") (pintype "unspecified"))
      (node (ref "U6") (pin "3") (pinfunction "3_3") (pintype "unspecified"))
      (node (ref "U6") (pin "4") (pinfunction "4_4") (pintype "unspecified"))
      (node (ref "U6") (pin "44") (pinfunction "44_44") (pintype "unspecified"))
    )
    (net (code "85") (name "GND") (class "Default")
      (node (ref "BT1") (pin "1") (pinfunction "1_1") (pintype "input"))
      (node (ref "C1") (pin "1") (pinfunction "1_1") (pintype "input"))
      (node (ref "C10") (pin "1") (pinfunction "1_1") (pintype "input"))
      (node (ref "C11") (pin "1") (pinfunction "1_1") (pintype "input"))
      (node (ref "C12") (pin "1") (pinfunction "1_1") (pintype "input"))
      (node (ref "C13") (pin "1") (pinfunction "1_1") (pintype "input"))
      (node (ref "C14") (pin "1") (pinfunction "1_1") (pintype "input"))
      (node (ref "C15") (pin "1") (pinfunction "1_1") (pintype "input"))
      (node (ref "C16") (pin "1") (pinfunction "1_1") (pintype "input"))
      (node (ref "C17") (pin "1") (pinfunction "1_1") (pintype "input"))
      (node (ref "C18") (pin "1") (pinfunction "1_1") (pintype "input"))
      (node (ref "C19") (pin "1") (pinfunction "1_1") (pintype "input"))
      (node (ref "C2") (pin "1") (pinfunction "1_1") (pintype "input"))
      (node (ref "C20") (pin "1") (pinfunction "1_1") (pintype "input"))
      (node (ref "C21") (pin "1") (pinfunction "1_1") (pintype "input"))
      (node (ref "C3") (pin "1") (pinfunction "1_1") (pintype "input"))
      (node (ref "C4") (pin "1") (pinfunction "1_1") (pintype "input"))
      (node (ref "C5") (pin "2") (pinfunction "2_2") (pintype "input"))
      (node (ref "C6") (pin "2") (pinfunction "2_2") (pintype "input"))
      (node (ref "C7") (pin "2") (pinfunction "2_2") (pintype "input"))
      (node (ref "C8") (pin "1") (pinfunction "1_1") (pintype "input"))
      (node (ref "CARD1") (pin "10") (pinfunction "10_10") (pintype "unspecified"))
      (node (ref "CARD1") (pin "11") (pinfunction "11_11") (pintype "unspecified"))
      (node (ref "CARD1") (pin "12") (pinfunction "12_12") (pintype "unspecified"))
      (node (ref "CARD1") (pin "13") (pinfunction "13_13") (pintype "unspecified"))
      (node (ref "CARD1") (pin "6") (pinfunction "VSS_6") (pintype "unspecified"))
      (node (ref "CARD1") (pin "CD") (pinfunction "CD_CD") (pintype "unspecified"))
      (node (ref "LED1") (pin "1") (pinfunction "C_1") (pintype "input"))
      (node (ref "P1") (pin "4") (pinfunction "4_4") (pintype "unspecified"))
      (node (ref "P2") (pin "4") (pinfunction "4_4") (pintype "unspecified"))
      (node (ref "R10") (pin "2") (pinfunction "2_2") (pintype "input"))
      (node (ref "R11") (pin "2") (pinfunction "2_2") (pintype "input"))
      (node (ref "R12") (pin "2") (pinfunction "2_2") (pintype "input"))
      (node (ref "R13") (pin "2") (pinfunction "2_2") (pintype "input"))
      (node (ref "SW1") (pin "2") (pinfunction "2_2") (pintype "input"))
      (node (ref "U1") (pin "10") (pinfunction "VSS_5_10") (pintype "input"))
      (node (ref "U1") (pin "27") (pinfunction "VSS_4_27") (pintype "input"))
      (node (ref "U1") (pin "74") (pinfunction "VSS_2_74") (pintype "input"))
      (node (ref "U1") (pin "99") (pinfunction "VSS_3_99") (pintype "input"))
      (node (ref "U2") (pin "1") (pinfunction "VBUS_1") (pintype "unspecified"))
      (node (ref "U2") (pin "6") (pinfunction "EP_6") (pintype "unspecified"))
      (node (ref "U2") (pin "7") (pinfunction "EP_7") (pintype "unspecified"))
      (node (ref "U2") (pin "8") (pinfunction "EP_8") (pintype "unspecified"))
      (node (ref "U2") (pin "9") (pinfunction "EP_9") (pintype "unspecified"))
      (node (ref "U3") (pin "1") (pinfunction "GND_1") (pintype "unspecified"))
      (node (ref "U4") (pin "4") (pinfunction "GND_4") (pintype "unspecified"))
      (node (ref "U5") (pin "1") (pinfunction "1_1") (pintype "unspecified"))
      (node (ref "U5") (pin "23") (pinfunction "23_23") (pintype "unspecified"))
      (node (ref "U5") (pin "24") (pinfunction "24_24") (pintype "unspecified"))
      (node (ref "U5") (pin "3") (pinfunction "3_3") (pintype "unspecified"))
      (node (ref "U5") (pin "41") (pinfunction "41_41") (pintype "unspecified"))
      (node (ref "U5") (pin "43") (pinfunction "43_43") (pintype "unspecified"))
      (node (ref "U5") (pin "8") (pinfunction "8_8") (pintype "unspecified"))
      (node (ref "U6") (pin "1") (pinfunction "1_1") (pintype "unspecified"))
      (node (ref "U6") (pin "14") (pinfunction "14_14") (pintype "unspecified"))
      (node (ref "U6") (pin "18") (pinfunction "18_18") (pintype "unspecified"))
      (node (ref "U6") (pin "22") (pinfunction "22_22") (pintype "unspecified"))
      (node (ref "U6") (pin "24") (pinfunction "24_24") (pintype "unspecified"))
      (node (ref "U6") (pin "28") (pinfunction "28_28") (pintype "unspecified"))
      (node (ref "U6") (pin "36") (pinfunction "36_36") (pintype "unspecified"))
      (node (ref "U6") (pin "43") (pinfunction "43_43") (pintype "unspecified"))
      (node (ref "U6") (pin "5") (pinfunction "5_5") (pintype "unspecified"))
    )
    (net (code "86") (name "Net-(BT1-Pad2)") (class "Default")
      (node (ref "BT1") (pin "2") (pinfunction "2_2") (pintype "input"))
      (node (ref "D1") (pin "2") (pinfunction "A_2") (pintype "unspecified"))
    )
    (net (code "87") (name "Net-(LED1-A)") (class "Default")
      (node (ref "LED1") (pin "2") (pinfunction "A_2") (pintype "input"))
      (node (ref "R4") (pin "1") (pinfunction "1_1") (pintype "input"))
    )
    (net (code "88") (name "Net-(U1-BOOT1{slash}PB2)") (class "Default")
      (node (ref "R11") (pin "1") (pinfunction "1_1") (pintype "input"))
      (node (ref "U1") (pin "37") (pinfunction "BOOT1/PB2_37") (pintype "input"))
    )
    (net (code "89") (name "Net-(U1-OSC_IN)") (class "Default")
      (node (ref "C10") (pin "2") (pinfunction "2_2") (pintype "input"))
      (node (ref "R16") (pin "2") (pinfunction "2_2") (pintype "input"))
      (node (ref "U1") (pin "12") (pinfunction "OSC_IN_12") (pintype "input"))
      (node (ref "X1") (pin "1") (pinfunction "OSC1_1") (pintype "input"))
    )
    (net (code "90") (name "Net-(U1-OSC_OUT)") (class "Default")
      (node (ref "C11") (pin "2") (pinfunction "2_2") (pintype "input"))
      (node (ref "R16") (pin "1") (pinfunction "1_1") (pintype "input"))
      (node (ref "U1") (pin "13") (pinfunction "OSC_OUT_13") (pintype "input"))
      (node (ref "X1") (pin "2") (pinfunction "OSC2_2") (pintype "input"))
    )
    (net (code "91") (name "Net-(U1-PC14{slash}OSC32_IN)") (class "Default")
      (node (ref "C12") (pin "2") (pinfunction "2_2") (pintype "input"))
      (node (ref "U1") (pin "8") (pinfunction "PC14/OSC32_IN_8") (pintype "input"))
      (node (ref "X2") (pin "2") (pinfunction "2_2") (pintype "input"))
    )
    (net (code "92") (name "Net-(U1-PC15{slash}OSC32_OUT)") (class "Default")
      (node (ref "C13") (pin "2") (pinfunction "2_2") (pintype "input"))
      (node (ref "U1") (pin "9") (pinfunction "PC15/OSC32_OUT_9") (pintype "input"))
      (node (ref "X2") (pin "1") (pinfunction "1_1") (pintype "input"))
    )
    (net (code "93") (name "Net-(U1-VCAP_1)") (class "Default")
      (node (ref "C14") (pin "2") (pinfunction "2_2") (pintype "input"))
      (node (ref "U1") (pin "49") (pinfunction "VCAP_1_49") (pintype "input"))
    )
    (net (code "94") (name "Net-(U1-VCAP_2)") (class "Default")
      (node (ref "C15") (pin "2") (pinfunction "2_2") (pintype "input"))
      (node (ref "U1") (pin "73") (pinfunction "VCAP_2_73") (pintype "input"))
    )
    (net (code "95") (name "Net-(U2-D+)") (class "Default")
      (node (ref "R1") (pin "2") (pinfunction "2_2") (pintype "input"))
      (node (ref "U2") (pin "2") (pinfunction "D+_2") (pintype "unspecified"))
    )
    (net (code "96") (name "Net-(U2-D-)") (class "Default")
      (node (ref "R2") (pin "2") (pinfunction "2_2") (pintype "input"))
      (node (ref "U2") (pin "3") (pinfunction "D-_3") (pintype "unspecified"))
    )
    (net (code "97") (name "unconnected-(U2-ID-Pad4)") (class "Default")
      (node (ref "U2") (pin "4") (pinfunction "ID_4") (pintype "unspecified+no_connect"))
    )
    (net (code "98") (name "unconnected-(U3-VOUT-Pad4)") (class "Default")
      (node (ref "U3") (pin "4") (pinfunction "VOUT_4") (pintype "unspecified+no_connect"))
    )
  )
)
